# FPGA_Conf.net
KiCad netlist of a schematic drawn in Altium Designer
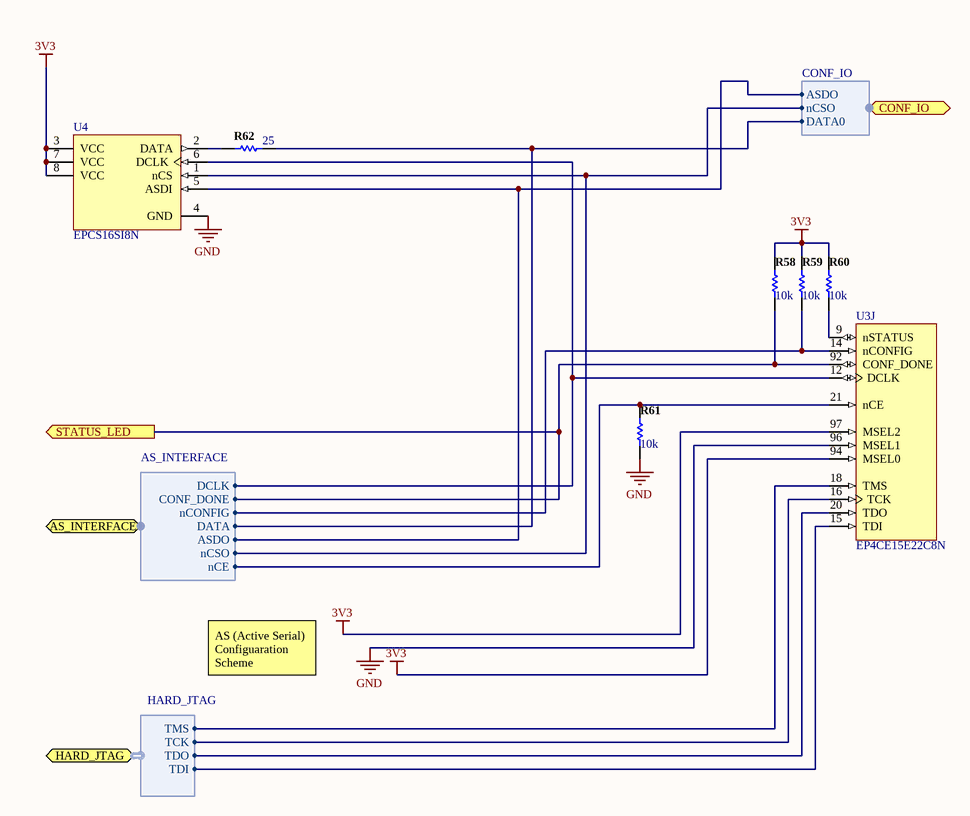
[diagram p0: FPGA_Conf.SchDoc]

(export (version "E")
  (design (tool "Eeschema 10.0.6"))
  (components
    (comp (ref "R58")
      (value "10k")
      (footprint "0805R-10K")
      (fields (field (name "TOLERANCE") "1 %"))
      (libsource (lib "AltiumDesignLibrary") (part "RES"))
    )
    (comp (ref "R59")
      (value "10k")
      (footprint "0805R-10K")
      (fields (field (name "TOLERANCE") "1 %"))
      (libsource (lib "AltiumDesignLibrary") (part "RES"))
    )
    (comp (ref "R60")
      (value "10k")
      (footprint "0805R-10K")
      (fields (field (name "TOLERANCE") "1 %"))
      (libsource (lib "AltiumDesignLibrary") (part "RES"))
    )
    (comp (ref "R61")
      (value "10k")
      (footprint "0805R-10K")
      (fields (field (name "TOLERANCE") "1 %"))
      (libsource (lib "AltiumDesignLibrary") (part "RES"))
    )
    (comp (ref "R62")
      (value "25")
      (footprint "0805R-0R1")
      (fields (field (name "TOLERANCE") "1 %"))
      (libsource (lib "AltiumDesignLibrary") (part "RES"))
    )
    (comp (ref "U3")
      (value "EP4CE15E22C8N")
      (footprint "EQFP144_A-165_D2-67_N")
      (fields (field (name "MANUFACTURER") "Altera"))
      (libsource (lib "Altera Cyclone IV E") (part "EP4CE15E22C8N"))
    )
    (comp (ref "U4")
      (value "EPCS16SI8N")
      (footprint "SOIC8_N")
      (libsource (lib "Altera EPCS") (part "EPCS16SI8N"))
    )
  )
  (nets
    (net (code "4") (name "/ASDO") (class "Default")
      (node (ref "U4") (pin "5") (pinfunction "ASDI_5") (pintype "input"))
    )
    (net (code "5") (name "/DATA") (class "Default")
      (node (ref "R62") (pin "2") (pinfunction "2_2") (pintype "passive"))
    )
    (net (code "6") (name "/DCLK") (class "Default")
      (node (ref "U3") (pin "12") (pinfunction "DCLK_12") (pintype "bidirectional"))
      (node (ref "U4") (pin "6") (pinfunction "DCLK_6") (pintype "input"))
    )
    (net (code "7") (name "/STATUS_LED") (class "Default")
      (node (ref "R58") (pin "2") (pinfunction "2_2") (pintype "passive"))
      (node (ref "U3") (pin "92") (pinfunction "CONF_DONE_92") (pintype "bidirectional"))
    )
    (net (code "8") (name "/TCK") (class "Default")
      (node (ref "U3") (pin "16") (pinfunction "TCK_16") (pintype "input"))
    )
    (net (code "9") (name "/TDI") (class "Default")
      (node (ref "U3") (pin "15") (pinfunction "TDI_15") (pintype "input"))
    )
    (net (code "10") (name "/TDO") (class "Default")
      (node (ref "U3") (pin "20") (pinfunction "TDO_20") (pintype "input"))
    )
    (net (code "11") (name "/TMS") (class "Default")
      (node (ref "U3") (pin "18") (pinfunction "TMS_18") (pintype "input"))
    )
    (net (code "12") (name "/nCE") (class "Default")
      (node (ref "R61") (pin "1") (pinfunction "1_1") (pintype "passive"))
      (node (ref "U3") (pin "21") (pinfunction "nCE_21") (pintype "input"))
    )
    (net (code "13") (name "/nCONFIG") (class "Default")
      (node (ref "R59") (pin "2") (pinfunction "2_2") (pintype "passive"))
      (node (ref "U3") (pin "14") (pinfunction "nCONFIG_14") (pintype "input"))
    )
    (net (code "14") (name "/nCSO") (class "Default")
      (node (ref "U4") (pin "1") (pinfunction "nCS_1") (pintype "input"))
    )
    (net (code "18") (name "3V3") (class "Default")
      (node (ref "R58") (pin "1") (pinfunction "1_1") (pintype "passive"))
      (node (ref "R59") (pin "1") (pinfunction "1_1") (pintype "passive"))
      (node (ref "R60") (pin "1") (pinfunction "1_1") (pintype "passive"))
      (node (ref "U3") (pin "94") (pinfunction "MSEL0_94") (pintype "input"))
      (node (ref "U3") (pin "97") (pinfunction "MSEL2_97") (pintype "input"))
      (node (ref "U4") (pin "3") (pinfunction "VCC_3") (pintype "power_in"))
      (node (ref "U4") (pin "7") (pinfunction "VCC_7") (pintype "power_in"))
      (node (ref "U4") (pin "8") (pinfunction "VCC_8") (pintype "power_in"))
    )
    (net (code "19") (name "GND") (class "Default")
      (node (ref "R61") (pin "2") (pinfunction "2_2") (pintype "passive"))
      (node (ref "U3") (pin "96") (pinfunction "MSEL1_96") (pintype "input"))
      (node (ref "U4") (pin "4") (pinfunction "GND_4") (pintype "power_in"))
    )
    (net (code "20") (name "Net-(U3J-nSTATUS)") (class "Default")
      (node (ref "R60") (pin "2") (pinfunction "2_2") (pintype "passive"))
      (node (ref "U3") (pin "9") (pinfunction "nSTATUS_9") (pintype "bidirectional"))
    )
    (net (code "21") (name "Net-(U4-DATA)") (class "Default")
      (node (ref "R62") (pin "1") (pinfunction "1_1") (pintype "passive"))
      (node (ref "U4") (pin "2") (pinfunction "DATA_2") (pintype "output"))
    )
  )
)
